# CAN_shield_rev1.net
KiCad netlist of a schematic drawn in EAGLE
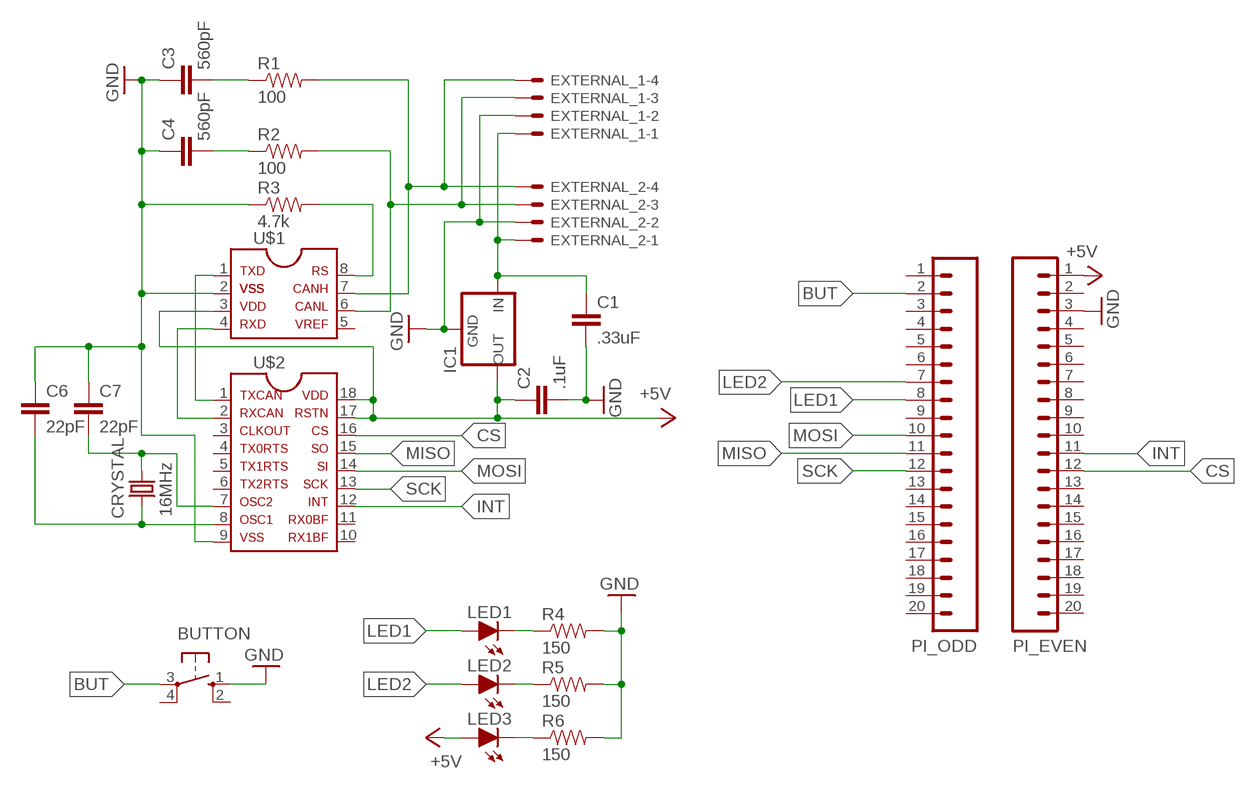
[diagram p0: schematic, sheet 1]

(export (version "E")
  (design (tool "Eeschema 10.0.6"))
  (components
    (comp (ref "BUTTON")
      (value "BTN_10-XX")
      (footprint "eagle-import:B3F-10XX")
      (fields (field (name "MPN") "B3F-1000"))
      (libsource (lib "eagle-import") (part "BTN_10-XX"))
    )
    (comp (ref "C1")
      (value ".33uF")
      (footprint "eagle-import:0805")
      (libsource (lib "eagle-import") (part "CAP0805"))
    )
    (comp (ref "C2")
      (value ".1uF")
      (footprint "eagle-import:0805")
      (libsource (lib "eagle-import") (part "CAP0805"))
    )
    (comp (ref "C3")
      (value "560pF")
      (footprint "eagle-import:0805")
      (libsource (lib "eagle-import") (part "CAP0805"))
    )
    (comp (ref "C4")
      (value "560pF")
      (footprint "eagle-import:0805")
      (libsource (lib "eagle-import") (part "CAP0805"))
    )
    (comp (ref "C6")
      (value "22pF")
      (footprint "eagle-import:0805")
      (libsource (lib "eagle-import") (part "CAP0805"))
    )
    (comp (ref "C7")
      (value "22pF")
      (footprint "eagle-import:0805")
      (libsource (lib "eagle-import") (part "CAP0805"))
    )
    (comp (ref "CRYSTAL")
      (value "16MHz")
      (footprint "eagle-import:HC49UP")
      (libsource (lib "eagle-import") (part "CRYSTALSMD"))
    )
    (comp (ref "EXTERNAL_1")
      (value "MINIFIT_5566-4")
      (footprint "eagle-import:MINIFIT_5566-4")
      (libsource (lib "eagle-import") (part "MINIFIT_5566-4"))
    )
    (comp (ref "EXTERNAL_2")
      (value "MINIFIT_5566-4")
      (footprint "eagle-import:MINIFIT_5566-4")
      (libsource (lib "eagle-import") (part "MINIFIT_5566-4"))
    )
    (comp (ref "IC1")
      (value "5VREG_L7805_HOR")
      (footprint "eagle-import:TO-220-H")
      (libsource (lib "eagle-import") (part "5VREG_L7805_HOR"))
    )
    (comp (ref "LED1")
      (value "LED-0805")
      (footprint "eagle-import:LED-805")
      (libsource (lib "eagle-import") (part "LED-0805"))
    )
    (comp (ref "LED2")
      (value "LED-0805")
      (footprint "eagle-import:LED-805")
      (libsource (lib "eagle-import") (part "LED-0805"))
    )
    (comp (ref "LED3")
      (value "LED-0805")
      (footprint "eagle-import:LED-805")
      (libsource (lib "eagle-import") (part "LED-0805"))
    )
    (comp (ref "PI_EVEN")
      (value "M20")
      (footprint "eagle-import:1X20")
      (libsource (lib "eagle-import") (part "M20"))
    )
    (comp (ref "PI_ODD")
      (value "M20")
      (footprint "eagle-import:1X20")
      (libsource (lib "eagle-import") (part "M20"))
    )
    (comp (ref "R1")
      (value "100")
      (footprint "eagle-import:0805")
      (libsource (lib "eagle-import") (part "RESISTOR0805-RES"))
    )
    (comp (ref "R2")
      (value "100")
      (footprint "eagle-import:0805")
      (libsource (lib "eagle-import") (part "RESISTOR0805-RES"))
    )
    (comp (ref "R3")
      (value "4.7k")
      (footprint "eagle-import:0805")
      (libsource (lib "eagle-import") (part "RESISTOR0805-RES"))
    )
    (comp (ref "R4")
      (value "150")
      (footprint "eagle-import:0805")
      (libsource (lib "eagle-import") (part "RESISTOR0805-RES"))
    )
    (comp (ref "R5")
      (value "150")
      (footprint "eagle-import:0805")
      (libsource (lib "eagle-import") (part "RESISTOR0805-RES"))
    )
    (comp (ref "R6")
      (value "150")
      (footprint "eagle-import:0805")
      (libsource (lib "eagle-import") (part "RESISTOR0805-RES"))
    )
    (comp (ref "U$1")
      (value "MCP2551")
      (footprint "eagle-import:SOIC-08")
      (libsource (lib "eagle-import") (part "MCP2551"))
    )
    (comp (ref "U$2")
      (value "MCP2515SMD")
      (footprint "eagle-import:SOIC-18W")
      (libsource (lib "eagle-import") (part "MCP2515SMD"))
    )
  )
  (nets
    (net (code "1") (name "+5V") (class "Default")
      (node (ref "C2") (pin "1") (pinfunction "1_1") (pintype "passive"))
      (node (ref "IC1") (pin "3") (pinfunction "OUT_3") (pintype "output"))
      (node (ref "LED3") (pin "A") (pinfunction "A_A") (pintype "passive"))
      (node (ref "PI_EVEN") (pin "1") (pinfunction "1_1") (pintype "passive"))
      (node (ref "U$1") (pin "3") (pinfunction "3_3") (pintype "passive"))
      (node (ref "U$2") (pin "17") (pinfunction "17_17") (pintype "passive"))
      (node (ref "U$2") (pin "18") (pinfunction "18_18") (pintype "passive"))
    )
    (net (code "2") (name "BUT") (class "Default")
      (node (ref "BUTTON") (pin "3") (pinfunction "P_3") (pintype "passive"))
      (node (ref "PI_ODD") (pin "2") (pinfunction "2_2") (pintype "passive"))
    )
    (net (code "3") (name "CS") (class "Default")
      (node (ref "PI_EVEN") (pin "12") (pinfunction "12_12") (pintype "passive"))
      (node (ref "U$2") (pin "16") (pinfunction "16_16") (pintype "passive"))
    )
    (net (code "4") (name "GND") (class "Default")
      (node (ref "BUTTON") (pin "1") (pinfunction "S_1") (pintype "passive"))
      (node (ref "C1") (pin "2") (pinfunction "2_2") (pintype "passive"))
      (node (ref "C2") (pin "2") (pinfunction "2_2") (pintype "passive"))
      (node (ref "C3") (pin "1") (pinfunction "1_1") (pintype "passive"))
      (node (ref "C4") (pin "1") (pinfunction "1_1") (pintype "passive"))
      (node (ref "C6") (pin "1") (pinfunction "1_1") (pintype "passive"))
      (node (ref "C7") (pin "1") (pinfunction "1_1") (pintype "passive"))
      (node (ref "EXTERNAL_1") (pin "2") (pinfunction "S_2") (pintype "passive"))
      (node (ref "EXTERNAL_2") (pin "2") (pinfunction "S_2") (pintype "passive"))
      (node (ref "IC1") (pin "2") (pinfunction "GND_2") (pintype "input"))
      (node (ref "PI_EVEN") (pin "3") (pinfunction "3_3") (pintype "passive"))
      (node (ref "R3") (pin "1") (pinfunction "1_1") (pintype "passive"))
      (node (ref "R4") (pin "2") (pinfunction "2_2") (pintype "passive"))
      (node (ref "R5") (pin "2") (pinfunction "2_2") (pintype "passive"))
      (node (ref "R6") (pin "2") (pinfunction "2_2") (pintype "passive"))
      (node (ref "U$1") (pin "2") (pinfunction "2_2") (pintype "passive"))
      (node (ref "U$2") (pin "9") (pinfunction "9_9") (pintype "passive"))
    )
    (net (code "5") (name "INT") (class "Default")
      (node (ref "PI_EVEN") (pin "11") (pinfunction "11_11") (pintype "passive"))
      (node (ref "U$2") (pin "12") (pinfunction "12_12") (pintype "passive"))
    )
    (net (code "6") (name "LED1") (class "Default")
      (node (ref "LED1") (pin "A") (pinfunction "A_A") (pintype "passive"))
      (node (ref "PI_ODD") (pin "8") (pinfunction "8_8") (pintype "passive"))
    )
    (net (code "7") (name "LED2") (class "Default")
      (node (ref "LED2") (pin "A") (pinfunction "A_A") (pintype "passive"))
      (node (ref "PI_ODD") (pin "7") (pinfunction "7_7") (pintype "passive"))
    )
    (net (code "8") (name "MISO") (class "Default")
      (node (ref "PI_ODD") (pin "11") (pinfunction "11_11") (pintype "passive"))
      (node (ref "U$2") (pin "15") (pinfunction "15_15") (pintype "passive"))
    )
    (net (code "9") (name "MOSI") (class "Default")
      (node (ref "PI_ODD") (pin "10") (pinfunction "10_10") (pintype "passive"))
      (node (ref "U$2") (pin "14") (pinfunction "14_14") (pintype "passive"))
    )
    (net (code "10") (name "Net-(C3-Pad2)") (class "Default")
      (node (ref "C3") (pin "2") (pinfunction "2_2") (pintype "passive"))
      (node (ref "R1") (pin "1") (pinfunction "1_1") (pintype "passive"))
    )
    (net (code "11") (name "Net-(C4-Pad2)") (class "Default")
      (node (ref "C4") (pin "2") (pinfunction "2_2") (pintype "passive"))
      (node (ref "R2") (pin "1") (pinfunction "1_1") (pintype "passive"))
    )
    (net (code "12") (name "Net-(C6-Pad2)") (class "Default")
      (node (ref "C6") (pin "2") (pinfunction "2_2") (pintype "passive"))
      (node (ref "CRYSTAL") (pin "2") (pinfunction "2_2") (pintype "passive"))
      (node (ref "U$2") (pin "8") (pinfunction "8_8") (pintype "passive"))
    )
    (net (code "13") (name "Net-(C7-Pad2)") (class "Default")
      (node (ref "C7") (pin "2") (pinfunction "2_2") (pintype "passive"))
      (node (ref "CRYSTAL") (pin "1") (pinfunction "1_1") (pintype "passive"))
      (node (ref "U$2") (pin "7") (pinfunction "7_7") (pintype "passive"))
    )
    (net (code "14") (name "Net-(EXTERNAL_1A-S)") (class "Default")
      (node (ref "C1") (pin "1") (pinfunction "1_1") (pintype "passive"))
      (node (ref "EXTERNAL_1") (pin "1") (pinfunction "S_1") (pintype "passive"))
      (node (ref "EXTERNAL_2") (pin "1") (pinfunction "S_1") (pintype "passive"))
      (node (ref "IC1") (pin "1") (pinfunction "IN_1") (pintype "input"))
    )
    (net (code "15") (name "Net-(EXTERNAL_1C-S)") (class "Default")
      (node (ref "EXTERNAL_1") (pin "3") (pinfunction "S_3") (pintype "passive"))
      (node (ref "EXTERNAL_2") (pin "3") (pinfunction "S_3") (pintype "passive"))
      (node (ref "R2") (pin "2") (pinfunction "2_2") (pintype "passive"))
      (node (ref "U$1") (pin "6") (pinfunction "6_6") (pintype "passive"))
    )
    (net (code "16") (name "Net-(EXTERNAL_1D-S)") (class "Default")
      (node (ref "EXTERNAL_1") (pin "4") (pinfunction "S_4") (pintype "passive"))
      (node (ref "EXTERNAL_2") (pin "4") (pinfunction "S_4") (pintype "passive"))
      (node (ref "R1") (pin "2") (pinfunction "2_2") (pintype "passive"))
      (node (ref "U$1") (pin "7") (pinfunction "7_7") (pintype "passive"))
    )
    (net (code "17") (name "Net-(LED1-PadC)") (class "Default")
      (node (ref "LED1") (pin "C") (pinfunction "C_C") (pintype "passive"))
      (node (ref "R4") (pin "1") (pinfunction "1_1") (pintype "passive"))
    )
    (net (code "18") (name "Net-(LED2-PadC)") (class "Default")
      (node (ref "LED2") (pin "C") (pinfunction "C_C") (pintype "passive"))
      (node (ref "R5") (pin "1") (pinfunction "1_1") (pintype "passive"))
    )
    (net (code "19") (name "Net-(LED3-PadC)") (class "Default")
      (node (ref "LED3") (pin "C") (pinfunction "C_C") (pintype "passive"))
      (node (ref "R6") (pin "1") (pinfunction "1_1") (pintype "passive"))
    )
    (net (code "20") (name "Net-(R3-Pad2)") (class "Default")
      (node (ref "R3") (pin "2") (pinfunction "2_2") (pintype "passive"))
      (node (ref "U$1") (pin "8") (pinfunction "8_8") (pintype "passive"))
    )
    (net (code "21") (name "Net-(U$1-Pad1)") (class "Default")
      (node (ref "U$1") (pin "1") (pinfunction "1_1") (pintype "passive"))
      (node (ref "U$2") (pin "1") (pinfunction "1_1") (pintype "passive"))
    )
    (net (code "22") (name "Net-(U$1-Pad4)") (class "Default")
      (node (ref "U$1") (pin "4") (pinfunction "4_4") (pintype "passive"))
      (node (ref "U$2") (pin "2") (pinfunction "2_2") (pintype "passive"))
    )
    (net (code "23") (name "SCK") (class "Default")
      (node (ref "PI_ODD") (pin "12") (pinfunction "12_12") (pintype "passive"))
      (node (ref "U$2") (pin "13") (pinfunction "13_13") (pintype "passive"))
    )
    (net (code "24") (name "unconnected-(BUTTON-P1-Pad4)") (class "Default")
      (node (ref "BUTTON") (pin "4") (pinfunction "P1_4") (pintype "passive"))
    )
    (net (code "25") (name "unconnected-(BUTTON-S1-Pad2)") (class "Default")
      (node (ref "BUTTON") (pin "2") (pinfunction "S1_2") (pintype "passive"))
    )
    (net (code "26") (name "unconnected-(PI_EVEN-Pad2)") (class "Default")
      (node (ref "PI_EVEN") (pin "2") (pinfunction "2_2") (pintype "passive"))
    )
    (net (code "27") (name "unconnected-(PI_EVEN-Pad4)") (class "Default")
      (node (ref "PI_EVEN") (pin "4") (pinfunction "4_4") (pintype "passive"))
    )
    (net (code "28") (name "unconnected-(PI_EVEN-Pad5)") (class "Default")
      (node (ref "PI_EVEN") (pin "5") (pinfunction "5_5") (pintype "passive"))
    )
    (net (code "29") (name "unconnected-(PI_EVEN-Pad6)") (class "Default")
      (node (ref "PI_EVEN") (pin "6") (pinfunction "6_6") (pintype "passive"))
    )
    (net (code "30") (name "unconnected-(PI_EVEN-Pad7)") (class "Default")
      (node (ref "PI_EVEN") (pin "7") (pinfunction "7_7") (pintype "passive"))
    )
    (net (code "31") (name "unconnected-(PI_EVEN-Pad8)") (class "Default")
      (node (ref "PI_EVEN") (pin "8") (pinfunction "8_8") (pintype "passive"))
    )
    (net (code "32") (name "unconnected-(PI_EVEN-Pad9)") (class "Default")
      (node (ref "PI_EVEN") (pin "9") (pinfunction "9_9") (pintype "passive"))
    )
    (net (code "33") (name "unconnected-(PI_EVEN-Pad10)") (class "Default")
      (node (ref "PI_EVEN") (pin "10") (pinfunction "10_10") (pintype "passive"))
    )
    (net (code "34") (name "unconnected-(PI_EVEN-Pad13)") (class "Default")
      (node (ref "PI_EVEN") (pin "13") (pinfunction "13_13") (pintype "passive"))
    )
    (net (code "35") (name "unconnected-(PI_EVEN-Pad14)") (class "Default")
      (node (ref "PI_EVEN") (pin "14") (pinfunction "14_14") (pintype "passive"))
    )
    (net (code "36") (name "unconnected-(PI_EVEN-Pad15)") (class "Default")
      (node (ref "PI_EVEN") (pin "15") (pinfunction "15_15") (pintype "passive"))
    )
    (net (code "37") (name "unconnected-(PI_EVEN-Pad16)") (class "Default")
      (node (ref "PI_EVEN") (pin "16") (pinfunction "16_16") (pintype "passive"))
    )
    (net (code "38") (name "unconnected-(PI_EVEN-Pad17)") (class "Default")
      (node (ref "PI_EVEN") (pin "17") (pinfunction "17_17") (pintype "passive"))
    )
    (net (code "39") (name "unconnected-(PI_EVEN-Pad18)") (class "Default")
      (node (ref "PI_EVEN") (pin "18") (pinfunction "18_18") (pintype "passive"))
    )
    (net (code "40") (name "unconnected-(PI_EVEN-Pad19)") (class "Default")
      (node (ref "PI_EVEN") (pin "19") (pinfunction "19_19") (pintype "passive"))
    )
    (net (code "41") (name "unconnected-(PI_EVEN-Pad20)") (class "Default")
      (node (ref "PI_EVEN") (pin "20") (pinfunction "20_20") (pintype "passive"))
    )
    (net (code "42") (name "unconnected-(PI_ODD-Pad1)") (class "Default")
      (node (ref "PI_ODD") (pin "1") (pinfunction "1_1") (pintype "passive"))
    )
    (net (code "43") (name "unconnected-(PI_ODD-Pad3)") (class "Default")
      (node (ref "PI_ODD") (pin "3") (pinfunction "3_3") (pintype "passive"))
    )
    (net (code "44") (name "unconnected-(PI_ODD-Pad4)") (class "Default")
      (node (ref "PI_ODD") (pin "4") (pinfunction "4_4") (pintype "passive"))
    )
    (net (code "45") (name "unconnected-(PI_ODD-Pad5)") (class "Default")
      (node (ref "PI_ODD") (pin "5") (pinfunction "5_5") (pintype "passive"))
    )
    (net (code "46") (name "unconnected-(PI_ODD-Pad6)") (class "Default")
      (node (ref "PI_ODD") (pin "6") (pinfunction "6_6") (pintype "passive"))
    )
    (net (code "47") (name "unconnected-(PI_ODD-Pad9)") (class "Default")
      (node (ref "PI_ODD") (pin "9") (pinfunction "9_9") (pintype "passive"))
    )
    (net (code "48") (name "unconnected-(PI_ODD-Pad13)") (class "Default")
      (node (ref "PI_ODD") (pin "13") (pinfunction "13_13") (pintype "passive"))
    )
    (net (code "49") (name "unconnected-(PI_ODD-Pad14)") (class "Default")
      (node (ref "PI_ODD") (pin "14") (pinfunction "14_14") (pintype "passive"))
    )
    (net (code "50") (name "unconnected-(PI_ODD-Pad15)") (class "Default")
      (node (ref "PI_ODD") (pin "15") (pinfunction "15_15") (pintype "passive"))
    )
    (net (code "51") (name "unconnected-(PI_ODD-Pad16)") (class "Default")
      (node (ref "PI_ODD") (pin "16") (pinfunction "16_16") (pintype "passive"))
    )
    (net (code "52") (name "unconnected-(PI_ODD-Pad17)") (class "Default")
      (node (ref "PI_ODD") (pin "17") (pinfunction "17_17") (pintype "passive"))
    )
    (net (code "53") (name "unconnected-(PI_ODD-Pad18)") (class "Default")
      (node (ref "PI_ODD") (pin "18") (pinfunction "18_18") (pintype "passive"))
    )
    (net (code "54") (name "unconnected-(PI_ODD-Pad19)") (class "Default")
      (node (ref "PI_ODD") (pin "19") (pinfunction "19_19") (pintype "passive"))
    )
    (net (code "55") (name "unconnected-(PI_ODD-Pad20)") (class "Default")
      (node (ref "PI_ODD") (pin "20") (pinfunction "20_20") (pintype "passive"))
    )
    (net (code "56") (name "unconnected-(U$1-Pad5)") (class "Default")
      (node (ref "U$1") (pin "5") (pinfunction "5_5") (pintype "passive"))
    )
    (net (code "57") (name "unconnected-(U$2-Pad3)") (class "Default")
      (node (ref "U$2") (pin "3") (pinfunction "3_3") (pintype "passive"))
    )
    (net (code "58") (name "unconnected-(U$2-Pad4)") (class "Default")
      (node (ref "U$2") (pin "4") (pinfunction "4_4") (pintype "passive"))
    )
    (net (code "59") (name "unconnected-(U$2-Pad5)") (class "Default")
      (node (ref "U$2") (pin "5") (pinfunction "5_5") (pintype "passive"))
    )
    (net (code "60") (name "unconnected-(U$2-Pad6)") (class "Default")
      (node (ref "U$2") (pin "6") (pinfunction "6_6") (pintype "passive"))
    )
    (net (code "61") (name "unconnected-(U$2-Pad10)") (class "Default")
      (node (ref "U$2") (pin "10") (pinfunction "10_10") (pintype "passive"))
    )
    (net (code "62") (name "unconnected-(U$2-Pad11)") (class "Default")
      (node (ref "U$2") (pin "11") (pinfunction "11_11") (pintype "passive"))
    )
  )
)
